# Rev_A.net
KiCad netlist of a schematic drawn in EAGLE
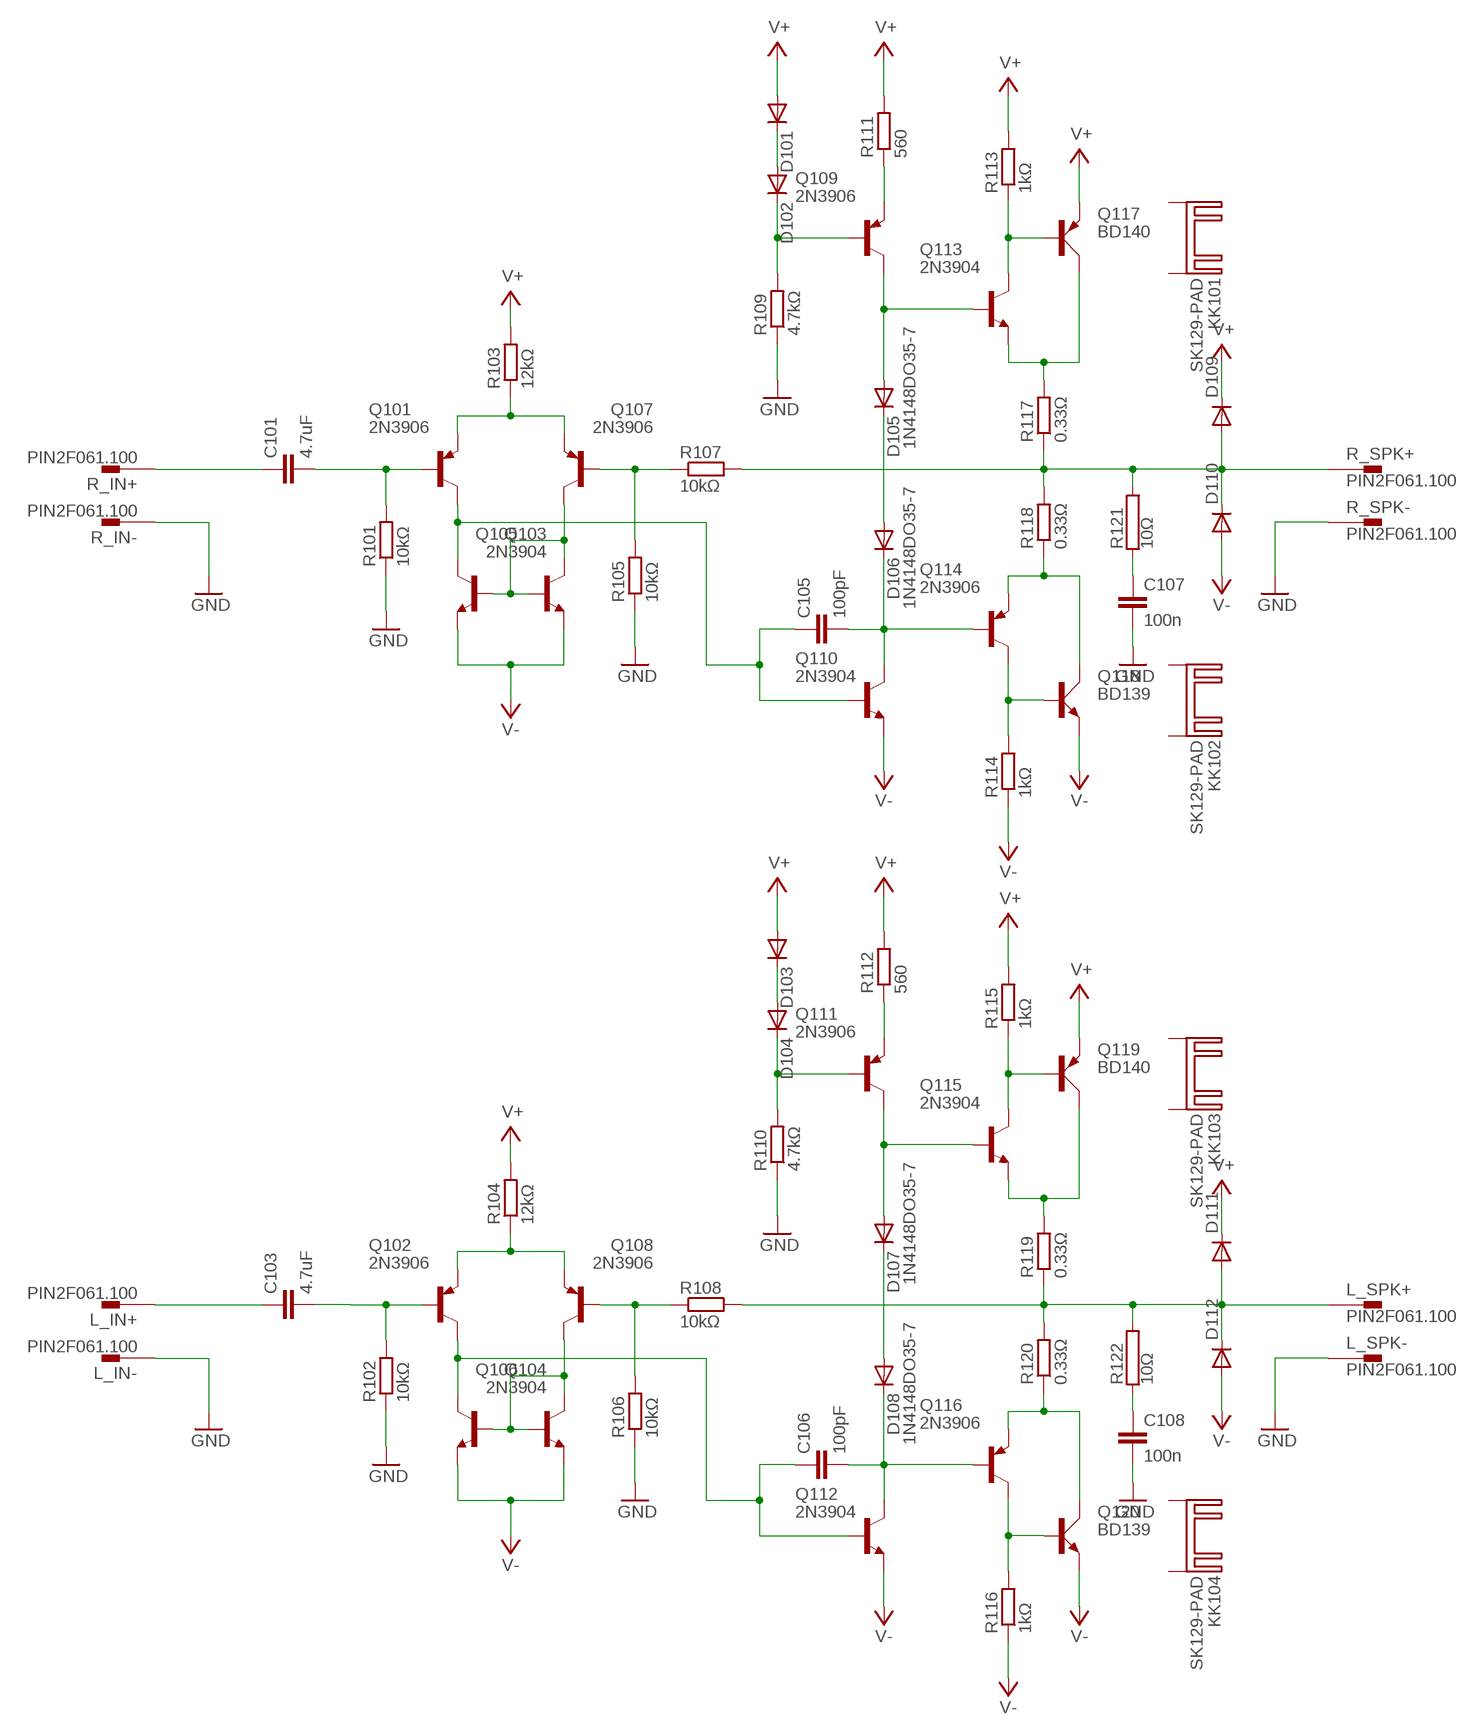
[diagram p0: schematic, sheet 1]
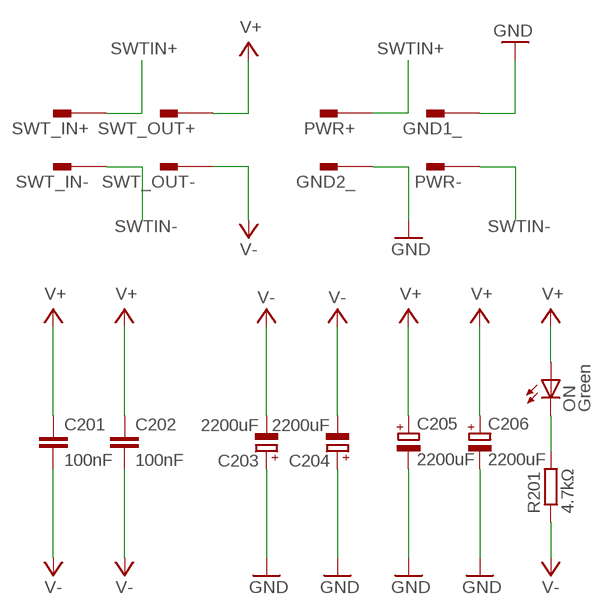
[diagram p1: schematic, sheet 2]

(export (version "E")
  (design (tool "Eeschema 10.0.6"))
  (components
    (comp (ref "C101")
      (value "4.7uF")
      (footprint "eagle-import:C225-113X268")
      (libsource (lib "eagle-import") (part "C-EU225-113X268"))
    )
    (comp (ref "C103")
      (value "4.7uF")
      (footprint "eagle-import:C225-113X268")
      (libsource (lib "eagle-import") (part "C-EU225-113X268"))
    )
    (comp (ref "C105")
      (value "100pF")
      (footprint "eagle-import:C050-050X075")
      (libsource (lib "eagle-import") (part "C-EU050-050X075"))
    )
    (comp (ref "C106")
      (value "100pF")
      (footprint "eagle-import:C050-050X075")
      (libsource (lib "eagle-import") (part "C-EU050-050X075"))
    )
    (comp (ref "C107")
      (value "100n")
      (footprint "eagle-import:C075-042X103")
      (libsource (lib "eagle-import") (part "C-EU075-042X103"))
    )
    (comp (ref "C108")
      (value "100n")
      (footprint "eagle-import:C075-042X103")
      (libsource (lib "eagle-import") (part "C-EU075-042X103"))
    )
    (comp (ref "D101")
      (value "1N4148DO35-7")
      (footprint "eagle-import:DO35-7")
      (libsource (lib "eagle-import") (part "1N4148DO35-7"))
    )
    (comp (ref "D102")
      (value "1N4148DO35-7")
      (footprint "eagle-import:DO35-7")
      (libsource (lib "eagle-import") (part "1N4148DO35-7"))
    )
    (comp (ref "D103")
      (value "1N4148DO35-7")
      (footprint "eagle-import:DO35-7")
      (libsource (lib "eagle-import") (part "1N4148DO35-7"))
    )
    (comp (ref "D104")
      (value "1N4148DO35-7")
      (footprint "eagle-import:DO35-7")
      (libsource (lib "eagle-import") (part "1N4148DO35-7"))
    )
    (comp (ref "D105")
      (value "1N4148DO35-7")
      (footprint "eagle-import:DO35-7")
      (libsource (lib "eagle-import") (part "1N4148DO35-7"))
    )
    (comp (ref "D106")
      (value "1N4148DO35-7")
      (footprint "eagle-import:DO35-7")
      (libsource (lib "eagle-import") (part "1N4148DO35-7"))
    )
    (comp (ref "D107")
      (value "1N4148DO35-7")
      (footprint "eagle-import:DO35-7")
      (libsource (lib "eagle-import") (part "1N4148DO35-7"))
    )
    (comp (ref "D108")
      (value "1N4148DO35-7")
      (footprint "eagle-import:DO35-7")
      (libsource (lib "eagle-import") (part "1N4148DO35-7"))
    )
    (comp (ref "D109")
      (value "1N4148DO35-7")
      (footprint "eagle-import:DO35-7")
      (libsource (lib "eagle-import") (part "1N4148DO35-7"))
    )
    (comp (ref "D110")
      (value "1N4148DO35-7")
      (footprint "eagle-import:DO35-7")
      (libsource (lib "eagle-import") (part "1N4148DO35-7"))
    )
    (comp (ref "D111")
      (value "1N4148DO35-7")
      (footprint "eagle-import:DO35-7")
      (libsource (lib "eagle-import") (part "1N4148DO35-7"))
    )
    (comp (ref "D112")
      (value "1N4148DO35-7")
      (footprint "eagle-import:DO35-7")
      (libsource (lib "eagle-import") (part "1N4148DO35-7"))
    )
    (comp (ref "KK101")
      (value "SK129-PAD")
      (footprint "eagle-import:SK129")
      (libsource (lib "eagle-import") (part "SK129-PAD"))
    )
    (comp (ref "KK102")
      (value "SK129-PAD")
      (footprint "eagle-import:SK129")
      (libsource (lib "eagle-import") (part "SK129-PAD"))
    )
    (comp (ref "KK103")
      (value "SK129-PAD")
      (footprint "eagle-import:SK129")
      (libsource (lib "eagle-import") (part "SK129-PAD"))
    )
    (comp (ref "KK104")
      (value "SK129-PAD")
      (footprint "eagle-import:SK129")
      (libsource (lib "eagle-import") (part "SK129-PAD"))
    )
    (comp (ref "L_IN+")
      (value "PIN2F061.100")
      (footprint "eagle-import:F061.100")
      (libsource (lib "eagle-import") (part "PIN2F061.100"))
    )
    (comp (ref "L_IN-")
      (value "PIN2F061.100")
      (footprint "eagle-import:F061.100")
      (libsource (lib "eagle-import") (part "PIN2F061.100"))
    )
    (comp (ref "L_SPK+")
      (value "PIN2F061.100")
      (footprint "eagle-import:F061.100")
      (libsource (lib "eagle-import") (part "PIN2F061.100"))
    )
    (comp (ref "L_SPK-")
      (value "PIN2F061.100")
      (footprint "eagle-import:F061.100")
      (libsource (lib "eagle-import") (part "PIN2F061.100"))
    )
    (comp (ref "Q101")
      (value "2N3906")
      (footprint "eagle-import:TO92")
      (libsource (lib "eagle-import") (part "2N3906"))
    )
    (comp (ref "Q102")
      (value "2N3906")
      (footprint "eagle-import:TO92")
      (libsource (lib "eagle-import") (part "2N3906"))
    )
    (comp (ref "Q103")
      (value "2N3904")
      (footprint "eagle-import:TO92")
      (libsource (lib "eagle-import") (part "2N3904"))
    )
    (comp (ref "Q104")
      (value "2N3904")
      (footprint "eagle-import:TO92")
      (libsource (lib "eagle-import") (part "2N3904"))
    )
    (comp (ref "Q105")
      (value "2N3904")
      (footprint "eagle-import:TO92")
      (libsource (lib "eagle-import") (part "2N3904"))
    )
    (comp (ref "Q106")
      (value "2N3904")
      (footprint "eagle-import:TO92")
      (libsource (lib "eagle-import") (part "2N3904"))
    )
    (comp (ref "Q107")
      (value "2N3906")
      (footprint "eagle-import:TO92")
      (libsource (lib "eagle-import") (part "2N3906"))
    )
    (comp (ref "Q108")
      (value "2N3906")
      (footprint "eagle-import:TO92")
      (libsource (lib "eagle-import") (part "2N3906"))
    )
    (comp (ref "Q109")
      (value "2N3906")
      (footprint "eagle-import:TO92")
      (libsource (lib "eagle-import") (part "2N3906"))
    )
    (comp (ref "Q110")
      (value "2N3904")
      (footprint "eagle-import:TO92")
      (libsource (lib "eagle-import") (part "2N3904"))
    )
    (comp (ref "Q111")
      (value "2N3906")
      (footprint "eagle-import:TO92")
      (libsource (lib "eagle-import") (part "2N3906"))
    )
    (comp (ref "Q112")
      (value "2N3904")
      (footprint "eagle-import:TO92")
      (libsource (lib "eagle-import") (part "2N3904"))
    )
    (comp (ref "Q113")
      (value "2N3904")
      (footprint "eagle-import:TO92")
      (libsource (lib "eagle-import") (part "2N3904"))
    )
    (comp (ref "Q114")
      (value "2N3906")
      (footprint "eagle-import:TO92")
      (libsource (lib "eagle-import") (part "2N3906"))
    )
    (comp (ref "Q115")
      (value "2N3904")
      (footprint "eagle-import:TO92")
      (libsource (lib "eagle-import") (part "2N3904"))
    )
    (comp (ref "Q116")
      (value "2N3906")
      (footprint "eagle-import:TO92")
      (libsource (lib "eagle-import") (part "2N3906"))
    )
    (comp (ref "Q117")
      (value "BD140")
      (footprint "eagle-import:TO126AV")
      (libsource (lib "eagle-import") (part "BD140"))
    )
    (comp (ref "Q118")
      (value "BD139")
      (footprint "eagle-import:TO126AV")
      (libsource (lib "eagle-import") (part "BD139"))
    )
    (comp (ref "Q119")
      (value "BD140")
      (footprint "eagle-import:TO126AV")
      (libsource (lib "eagle-import") (part "BD140"))
    )
    (comp (ref "Q120")
      (value "BD139")
      (footprint "eagle-import:TO126AV")
      (libsource (lib "eagle-import") (part "BD139"))
    )
    (comp (ref "R101")
      (value "10kΩ")
      (footprint "eagle-import:0207_10")
      (libsource (lib "eagle-import") (part "R-EU_0207/10"))
    )
    (comp (ref "R102")
      (value "10kΩ")
      (footprint "eagle-import:0207_10")
      (libsource (lib "eagle-import") (part "R-EU_0207/10"))
    )
    (comp (ref "R103")
      (value "12kΩ")
      (footprint "eagle-import:0207_10")
      (libsource (lib "eagle-import") (part "R-EU_0207/10"))
    )
    (comp (ref "R104")
      (value "12kΩ")
      (footprint "eagle-import:0207_10")
      (libsource (lib "eagle-import") (part "R-EU_0207/10"))
    )
    (comp (ref "R105")
      (value "10kΩ")
      (footprint "eagle-import:0207_10")
      (libsource (lib "eagle-import") (part "R-EU_0207/10"))
    )
    (comp (ref "R106")
      (value "10kΩ")
      (footprint "eagle-import:0207_10")
      (libsource (lib "eagle-import") (part "R-EU_0207/10"))
    )
    (comp (ref "R107")
      (value "10kΩ")
      (footprint "eagle-import:0207_10")
      (libsource (lib "eagle-import") (part "R-EU_0207/10"))
    )
    (comp (ref "R108")
      (value "10kΩ")
      (footprint "eagle-import:0207_10")
      (libsource (lib "eagle-import") (part "R-EU_0207/10"))
    )
    (comp (ref "R109")
      (value "4.7kΩ")
      (footprint "eagle-import:0207_10")
      (libsource (lib "eagle-import") (part "R-EU_0207/10"))
    )
    (comp (ref "R110")
      (value "4.7kΩ")
      (footprint "eagle-import:0207_10")
      (libsource (lib "eagle-import") (part "R-EU_0207/10"))
    )
    (comp (ref "R111")
      (value "560")
      (footprint "eagle-import:0207_10")
      (libsource (lib "eagle-import") (part "R-EU_0207/10"))
    )
    (comp (ref "R112")
      (value "560")
      (footprint "eagle-import:0207_10")
      (libsource (lib "eagle-import") (part "R-EU_0207/10"))
    )
    (comp (ref "R113")
      (value "1kΩ")
      (footprint "eagle-import:0207_10")
      (libsource (lib "eagle-import") (part "R-EU_0207/10"))
    )
    (comp (ref "R114")
      (value "1kΩ")
      (footprint "eagle-import:0207_10")
      (libsource (lib "eagle-import") (part "R-EU_0207/10"))
    )
    (comp (ref "R115")
      (value "1kΩ")
      (footprint "eagle-import:0207_10")
      (libsource (lib "eagle-import") (part "R-EU_0207/10"))
    )
    (comp (ref "R116")
      (value "1kΩ")
      (footprint "eagle-import:0207_10")
      (libsource (lib "eagle-import") (part "R-EU_0207/10"))
    )
    (comp (ref "R117")
      (value "0.33Ω")
      (footprint "eagle-import:0309_12")
      (libsource (lib "eagle-import") (part "R-EU_0309/12"))
    )
    (comp (ref "R118")
      (value "0.33Ω")
      (footprint "eagle-import:0309_12")
      (libsource (lib "eagle-import") (part "R-EU_0309/12"))
    )
    (comp (ref "R119")
      (value "0.33Ω")
      (footprint "eagle-import:0309_12")
      (libsource (lib "eagle-import") (part "R-EU_0309/12"))
    )
    (comp (ref "R120")
      (value "0.33Ω")
      (footprint "eagle-import:0309_12")
      (libsource (lib "eagle-import") (part "R-EU_0309/12"))
    )
    (comp (ref "R121")
      (value "10Ω")
      (footprint "eagle-import:MNS-5")
      (libsource (lib "eagle-import") (part "RMNS-5"))
    )
    (comp (ref "R122")
      (value "10Ω")
      (footprint "eagle-import:MNS-5")
      (libsource (lib "eagle-import") (part "RMNS-5"))
    )
    (comp (ref "R_IN+")
      (value "PIN2F061.100")
      (footprint "eagle-import:F061.100")
      (libsource (lib "eagle-import") (part "PIN2F061.100"))
    )
    (comp (ref "R_IN-")
      (value "PIN2F061.100")
      (footprint "eagle-import:F061.100")
      (libsource (lib "eagle-import") (part "PIN2F061.100"))
    )
    (comp (ref "R_SPK+")
      (value "PIN2F061.100")
      (footprint "eagle-import:F061.100")
      (libsource (lib "eagle-import") (part "PIN2F061.100"))
    )
    (comp (ref "R_SPK-")
      (value "PIN2F061.100")
      (footprint "eagle-import:F061.100")
      (libsource (lib "eagle-import") (part "PIN2F061.100"))
    )
    (comp (ref "C201")
      (value "100nF")
      (footprint "eagle-import:C025-025X050")
      (libsource (lib "eagle-import") (part "C-EU025-025X050"))
    )
    (comp (ref "C202")
      (value "100nF")
      (footprint "eagle-import:C025-025X050")
      (libsource (lib "eagle-import") (part "C-EU025-025X050"))
    )
    (comp (ref "C203")
      (value "2200uF")
      (footprint "eagle-import:E5-10,5")
      (libsource (lib "eagle-import") (part "CPOL-EUE5-10.5"))
    )
    (comp (ref "C204")
      (value "2200uF")
      (footprint "eagle-import:E5-10,5")
      (libsource (lib "eagle-import") (part "CPOL-EUE5-10.5"))
    )
    (comp (ref "C205")
      (value "2200uF")
      (footprint "eagle-import:E5-10,5")
      (libsource (lib "eagle-import") (part "CPOL-EUE5-10.5"))
    )
    (comp (ref "C206")
      (value "2200uF")
      (footprint "eagle-import:E5-10,5")
      (libsource (lib "eagle-import") (part "CPOL-EUE5-10.5"))
    )
    (comp (ref "GND1_")
      (value "PIN2F061.100")
      (footprint "eagle-import:F061.100")
      (libsource (lib "eagle-import") (part "PIN2F061.100"))
    )
    (comp (ref "GND2_")
      (value "PIN2F061.100")
      (footprint "eagle-import:F061.100")
      (libsource (lib "eagle-import") (part "PIN2F061.100"))
    )
    (comp (ref "ON")
      (value "Green")
      (footprint "eagle-import:LED5MM")
      (libsource (lib "eagle-import") (part "LED5MM"))
    )
    (comp (ref "PWR+")
      (value "PIN2F061.100")
      (footprint "eagle-import:F061.100")
      (libsource (lib "eagle-import") (part "PIN2F061.100"))
    )
    (comp (ref "PWR-")
      (value "PIN2F061.100")
      (footprint "eagle-import:F061.100")
      (libsource (lib "eagle-import") (part "PIN2F061.100"))
    )
    (comp (ref "R201")
      (value "4.7kΩ")
      (footprint "eagle-import:0207_10")
      (libsource (lib "eagle-import") (part "R-EU_0207/10"))
    )
    (comp (ref "SWT_IN+")
      (value "PIN2F061.100")
      (footprint "eagle-import:F061.100")
      (libsource (lib "eagle-import") (part "PIN2F061.100"))
    )
    (comp (ref "SWT_IN-")
      (value "PIN2F061.100")
      (footprint "eagle-import:F061.100")
      (libsource (lib "eagle-import") (part "PIN2F061.100"))
    )
    (comp (ref "SWT_OUT+")
      (value "PIN2F061.100")
      (footprint "eagle-import:F061.100")
      (libsource (lib "eagle-import") (part "PIN2F061.100"))
    )
    (comp (ref "SWT_OUT-")
      (value "PIN2F061.100")
      (footprint "eagle-import:F061.100")
      (libsource (lib "eagle-import") (part "PIN2F061.100"))
    )
  )
  (nets
    (net (code "1") (name "GND") (class "Default")
      (node (ref "C107") (pin "2") (pinfunction "2_2") (pintype "passive"))
      (node (ref "C108") (pin "2") (pinfunction "2_2") (pintype "passive"))
      (node (ref "C203") (pin "+") (pinfunction "+_+") (pintype "passive"))
      (node (ref "C204") (pin "+") (pinfunction "+_+") (pintype "passive"))
      (node (ref "C205") (pin "-") (pinfunction "-_-") (pintype "passive"))
      (node (ref "C206") (pin "-") (pinfunction "-_-") (pintype "passive"))
      (node (ref "GND1_") (pin "A1") (pinfunction "1_A1") (pintype "passive"))
      (node (ref "GND1_") (pin "A2") (pinfunction "1_A2") (pintype "passive"))
      (node (ref "GND2_") (pin "A1") (pinfunction "1_A1") (pintype "passive"))
      (node (ref "GND2_") (pin "A2") (pinfunction "1_A2") (pintype "passive"))
      (node (ref "L_IN-") (pin "A1") (pinfunction "1_A1") (pintype "passive"))
      (node (ref "L_IN-") (pin "A2") (pinfunction "1_A2") (pintype "passive"))
      (node (ref "L_SPK-") (pin "A1") (pinfunction "1_A1") (pintype "passive"))
      (node (ref "L_SPK-") (pin "A2") (pinfunction "1_A2") (pintype "passive"))
      (node (ref "R101") (pin "1") (pinfunction "1_1") (pintype "passive"))
      (node (ref "R102") (pin "1") (pinfunction "1_1") (pintype "passive"))
      (node (ref "R105") (pin "1") (pinfunction "1_1") (pintype "passive"))
      (node (ref "R106") (pin "1") (pinfunction "1_1") (pintype "passive"))
      (node (ref "R109") (pin "1") (pinfunction "1_1") (pintype "passive"))
      (node (ref "R110") (pin "1") (pinfunction "1_1") (pintype "passive"))
      (node (ref "R_IN-") (pin "A1") (pinfunction "1_A1") (pintype "passive"))
      (node (ref "R_IN-") (pin "A2") (pinfunction "1_A2") (pintype "passive"))
      (node (ref "R_SPK-") (pin "A1") (pinfunction "1_A1") (pintype "passive"))
      (node (ref "R_SPK-") (pin "A2") (pinfunction "1_A2") (pintype "passive"))
    )
    (net (code "2") (name "Net-(C101-Pad1)") (class "Default")
      (node (ref "C101") (pin "1") (pinfunction "1_1") (pintype "passive"))
      (node (ref "R_IN+") (pin "A1") (pinfunction "1_A1") (pintype "passive"))
      (node (ref "R_IN+") (pin "A2") (pinfunction "1_A2") (pintype "passive"))
    )
    (net (code "3") (name "Net-(C103-Pad1)") (class "Default")
      (node (ref "C103") (pin "1") (pinfunction "1_1") (pintype "passive"))
      (node (ref "L_IN+") (pin "A1") (pinfunction "1_A1") (pintype "passive"))
      (node (ref "L_IN+") (pin "A2") (pinfunction "1_A2") (pintype "passive"))
    )
    (net (code "4") (name "Net-(C107-Pad1)") (class "Default")
      (node (ref "C107") (pin "1") (pinfunction "1_1") (pintype "passive"))
      (node (ref "R121") (pin "1") (pinfunction "1_1") (pintype "passive"))
    )
    (net (code "5") (name "Net-(C108-Pad1)") (class "Default")
      (node (ref "C108") (pin "1") (pinfunction "1_1") (pintype "passive"))
      (node (ref "R122") (pin "1") (pinfunction "1_1") (pintype "passive"))
    )
    (net (code "6") (name "Net-(D101-PadC)") (class "Default")
      (node (ref "D101") (pin "C") (pinfunction "C_C") (pintype "passive"))
      (node (ref "D102") (pin "A") (pinfunction "A_A") (pintype "passive"))
    )
    (net (code "7") (name "Net-(D103-PadC)") (class "Default")
      (node (ref "D103") (pin "C") (pinfunction "C_C") (pintype "passive"))
      (node (ref "D104") (pin "A") (pinfunction "A_A") (pintype "passive"))
    )
    (net (code "8") (name "Net-(D105-PadC)") (class "Default")
      (node (ref "D105") (pin "C") (pinfunction "C_C") (pintype "passive"))
      (node (ref "D106") (pin "A") (pinfunction "A_A") (pintype "passive"))
    )
    (net (code "9") (name "Net-(D107-PadC)") (class "Default")
      (node (ref "D107") (pin "C") (pinfunction "C_C") (pintype "passive"))
      (node (ref "D108") (pin "A") (pinfunction "A_A") (pintype "passive"))
    )
    (net (code "10") (name "Net-(D109-PadA)") (class "Default")
      (node (ref "D109") (pin "A") (pinfunction "A_A") (pintype "passive"))
      (node (ref "D110") (pin "C") (pinfunction "C_C") (pintype "passive"))
      (node (ref "R107") (pin "2") (pinfunction "2_2") (pintype "passive"))
      (node (ref "R117") (pin "1") (pinfunction "1_1") (pintype "passive"))
      (node (ref "R118") (pin "2") (pinfunction "2_2") (pintype "passive"))
      (node (ref "R121") (pin "2") (pinfunction "2_2") (pintype "passive"))
      (node (ref "R_SPK+") (pin "A1") (pinfunction "1_A1") (pintype "passive"))
      (node (ref "R_SPK+") (pin "A2") (pinfunction "1_A2") (pintype "passive"))
    )
    (net (code "11") (name "Net-(D111-PadA)") (class "Default")
      (node (ref "D111") (pin "A") (pinfunction "A_A") (pintype "passive"))
      (node (ref "D112") (pin "C") (pinfunction "C_C") (pintype "passive"))
      (node (ref "L_SPK+") (pin "A1") (pinfunction "1_A1") (pintype "passive"))
      (node (ref "L_SPK+") (pin "A2") (pinfunction "1_A2") (pintype "passive"))
      (node (ref "R108") (pin "2") (pinfunction "2_2") (pintype "passive"))
      (node (ref "R119") (pin "1") (pinfunction "1_1") (pintype "passive"))
      (node (ref "R120") (pin "2") (pinfunction "2_2") (pintype "passive"))
      (node (ref "R122") (pin "2") (pinfunction "2_2") (pintype "passive"))
    )
    (net (code "12") (name "Net-(ON-C)") (class "Default")
      (node (ref "ON") (pin "K") (pinfunction "C_K") (pintype "passive"))
      (node (ref "R201") (pin "2") (pinfunction "2_2") (pintype "passive"))
    )
    (net (code "13") (name "Net-(Q101-B)") (class "Default")
      (node (ref "C101") (pin "2") (pinfunction "2_2") (pintype "passive"))
      (node (ref "Q101") (pin "2") (pinfunction "B_2") (pintype "passive"))
      (node (ref "R101") (pin "2") (pinfunction "2_2") (pintype "passive"))
    )
    (net (code "14") (name "Net-(Q101-C)") (class "Default")
      (node (ref "C105") (pin "1") (pinfunction "1_1") (pintype "passive"))
      (node (ref "Q101") (pin "1") (pinfunction "C_1") (pintype "passive"))
      (node (ref "Q103") (pin "1") (pinfunction "C_1") (pintype "passive"))
      (node (ref "Q110") (pin "2") (pinfunction "B_2") (pintype "passive"))
    )
    (net (code "15") (name "Net-(Q101-E)") (class "Default")
      (node (ref "Q101") (pin "3") (pinfunction "E_3") (pintype "passive"))
      (node (ref "Q107") (pin "3") (pinfunction "E_3") (pintype "passive"))
      (node (ref "R103") (pin "1") (pinfunction "1_1") (pintype "passive"))
    )
    (net (code "16") (name "Net-(Q102-B)") (class "Default")
      (node (ref "C103") (pin "2") (pinfunction "2_2") (pintype "passive"))
      (node (ref "Q102") (pin "2") (pinfunction "B_2") (pintype "passive"))
      (node (ref "R102") (pin "2") (pinfunction "2_2") (pintype "passive"))
    )
    (net (code "17") (name "Net-(Q102-C)") (class "Default")
      (node (ref "C106") (pin "1") (pinfunction "1_1") (pintype "passive"))
      (node (ref "Q102") (pin "1") (pinfunction "C_1") (pintype "passive"))
      (node (ref "Q104") (pin "1") (pinfunction "C_1") (pintype "passive"))
      (node (ref "Q112") (pin "2") (pinfunction "B_2") (pintype "passive"))
    )
    (net (code "18") (name "Net-(Q102-E)") (class "Default")
      (node (ref "Q102") (pin "3") (pinfunction "E_3") (pintype "passive"))
      (node (ref "Q108") (pin "3") (pinfunction "E_3") (pintype "passive"))
      (node (ref "R104") (pin "1") (pinfunction "1_1") (pintype "passive"))
    )
    (net (code "19") (name "Net-(Q103-B)") (class "Default")
      (node (ref "Q103") (pin "2") (pinfunction "B_2") (pintype "passive"))
      (node (ref "Q105") (pin "1") (pinfunction "C_1") (pintype "passive"))
      (node (ref "Q105") (pin "2") (pinfunction "B_2") (pintype "passive"))
      (node (ref "Q107") (pin "1") (pinfunction "C_1") (pintype "passive"))
    )
    (net (code "20") (name "Net-(Q104-B)") (class "Default")
      (node (ref "Q104") (pin "2") (pinfunction "B_2") (pintype "passive"))
      (node (ref "Q106") (pin "1") (pinfunction "C_1") (pintype "passive"))
      (node (ref "Q106") (pin "2") (pinfunction "B_2") (pintype "passive"))
      (node (ref "Q108") (pin "1") (pinfunction "C_1") (pintype "passive"))
    )
    (net (code "21") (name "Net-(Q107-B)") (class "Default")
      (node (ref "Q107") (pin "2") (pinfunction "B_2") (pintype "passive"))
      (node (ref "R105") (pin "2") (pinfunction "2_2") (pintype "passive"))
      (node (ref "R107") (pin "1") (pinfunction "1_1") (pintype "passive"))
    )
    (net (code "22") (name "Net-(Q108-B)") (class "Default")
      (node (ref "Q108") (pin "2") (pinfunction "B_2") (pintype "passive"))
      (node (ref "R106") (pin "2") (pinfunction "2_2") (pintype "passive"))
      (node (ref "R108") (pin "1") (pinfunction "1_1") (pintype "passive"))
    )
    (net (code "23") (name "Net-(Q109-B)") (class "Default")
      (node (ref "D102") (pin "C") (pinfunction "C_C") (pintype "passive"))
      (node (ref "Q109") (pin "2") (pinfunction "B_2") (pintype "passive"))
      (node (ref "R109") (pin "2") (pinfunction "2_2") (pintype "passive"))
    )
    (net (code "24") (name "Net-(Q109-C)") (class "Default")
      (node (ref "D105") (pin "A") (pinfunction "A_A") (pintype "passive"))
      (node (ref "Q109") (pin "1") (pinfunction "C_1") (pintype "passive"))
      (node (ref "Q113") (pin "2") (pinfunction "B_2") (pintype "passive"))
    )
    (net (code "25") (name "Net-(Q109-E)") (class "Default")
      (node (ref "Q109") (pin "3") (pinfunction "E_3") (pintype "passive"))
      (node (ref "R111") (pin "1") (pinfunction "1_1") (pintype "passive"))
    )
    (net (code "26") (name "Net-(Q110-C)") (class "Default")
      (node (ref "C105") (pin "2") (pinfunction "2_2") (pintype "passive"))
      (node (ref "D106") (pin "C") (pinfunction "C_C") (pintype "passive"))
      (node (ref "Q110") (pin "1") (pinfunction "C_1") (pintype "passive"))
      (node (ref "Q114") (pin "2") (pinfunction "B_2") (pintype "passive"))
    )
    (net (code "27") (name "Net-(Q111-B)") (class "Default")
      (node (ref "D104") (pin "C") (pinfunction "C_C") (pintype "passive"))
      (node (ref "Q111") (pin "2") (pinfunction "B_2") (pintype "passive"))
      (node (ref "R110") (pin "2") (pinfunction "2_2") (pintype "passive"))
    )
    (net (code "28") (name "Net-(Q111-C)") (class "Default")
      (node (ref "D107") (pin "A") (pinfunction "A_A") (pintype "passive"))
      (node (ref "Q111") (pin "1") (pinfunction "C_1") (pintype "passive"))
      (node (ref "Q115") (pin "2") (pinfunction "B_2") (pintype "passive"))
    )
    (net (code "29") (name "Net-(Q111-E)") (class "Default")
      (node (ref "Q111") (pin "3") (pinfunction "E_3") (pintype "passive"))
      (node (ref "R112") (pin "1") (pinfunction "1_1") (pintype "passive"))
    )
    (net (code "30") (name "Net-(Q112-C)") (class "Default")
      (node (ref "C106") (pin "2") (pinfunction "2_2") (pintype "passive"))
      (node (ref "D108") (pin "C") (pinfunction "C_C") (pintype "passive"))
      (node (ref "Q112") (pin "1") (pinfunction "C_1") (pintype "passive"))
      (node (ref "Q116") (pin "2") (pinfunction "B_2") (pintype "passive"))
    )
    (net (code "31") (name "Net-(Q113-C)") (class "Default")
      (node (ref "Q113") (pin "1") (pinfunction "C_1") (pintype "passive"))
      (node (ref "Q117") (pin "B") (pinfunction "B_B") (pintype "passive"))
      (node (ref "R113") (pin "1") (pinfunction "1_1") (pintype "passive"))
    )
    (net (code "32") (name "Net-(Q113-E)") (class "Default")
      (node (ref "Q113") (pin "3") (pinfunction "E_3") (pintype "passive"))
      (node (ref "Q117") (pin "C") (pinfunction "C_C") (pintype "passive"))
      (node (ref "R117") (pin "2") (pinfunction "2_2") (pintype "passive"))
    )
    (net (code "33") (name "Net-(Q114-C)") (class "Default")
      (node (ref "Q114") (pin "1") (pinfunction "C_1") (pintype "passive"))
      (node (ref "Q118") (pin "B") (pinfunction "B_B") (pintype "passive"))
      (node (ref "R114") (pin "2") (pinfunction "2_2") (pintype "passive"))
    )
    (net (code "34") (name "Net-(Q114-E)") (class "Default")
      (node (ref "Q114") (pin "3") (pinfunction "E_3") (pintype "passive"))
      (node (ref "Q118") (pin "C") (pinfunction "C_C") (pintype "passive"))
      (node (ref "R118") (pin "1") (pinfunction "1_1") (pintype "passive"))
    )
    (net (code "35") (name "Net-(Q115-C)") (class "Default")
      (node (ref "Q115") (pin "1") (pinfunction "C_1") (pintype "passive"))
      (node (ref "Q119") (pin "B") (pinfunction "B_B") (pintype "passive"))
      (node (ref "R115") (pin "1") (pinfunction "1_1") (pintype "passive"))
    )
    (net (code "36") (name "Net-(Q115-E)") (class "Default")
      (node (ref "Q115") (pin "3") (pinfunction "E_3") (pintype "passive"))
      (node (ref "Q119") (pin "C") (pinfunction "C_C") (pintype "passive"))
      (node (ref "R119") (pin "2") (pinfunction "2_2") (pintype "passive"))
    )
    (net (code "37") (name "Net-(Q116-C)") (class "Default")
      (node (ref "Q116") (pin "1") (pinfunction "C_1") (pintype "passive"))
      (node (ref "Q120") (pin "B") (pinfunction "B_B") (pintype "passive"))
      (node (ref "R116") (pin "2") (pinfunction "2_2") (pintype "passive"))
    )
    (net (code "38") (name "Net-(Q116-E)") (class "Default")
      (node (ref "Q116") (pin "3") (pinfunction "E_3") (pintype "passive"))
      (node (ref "Q120") (pin "C") (pinfunction "C_C") (pintype "passive"))
      (node (ref "R120") (pin "1") (pinfunction "1_1") (pintype "passive"))
    )
    (net (code "39") (name "SWTIN+") (class "Default")
      (node (ref "PWR+") (pin "A1") (pinfunction "1_A1") (pintype "passive"))
      (node (ref "PWR+") (pin "A2") (pinfunction "1_A2") (pintype "passive"))
      (node (ref "SWT_IN+") (pin "A1") (pinfunction "1_A1") (pintype "passive"))
      (node (ref "SWT_IN+") (pin "A2") (pinfunction "1_A2") (pintype "passive"))
    )
    (net (code "40") (name "SWTIN-") (class "Default")
      (node (ref "PWR-") (pin "A1") (pinfunction "1_A1") (pintype "passive"))
      (node (ref "PWR-") (pin "A2") (pinfunction "1_A2") (pintype "passive"))
      (node (ref "SWT_IN-") (pin "A1") (pinfunction "1_A1") (pintype "passive"))
      (node (ref "SWT_IN-") (pin "A2") (pinfunction "1_A2") (pintype "passive"))
    )
    (net (code "41") (name "V+") (class "Default")
      (node (ref "C201") (pin "1") (pinfunction "1_1") (pintype "passive"))
      (node (ref "C202") (pin "1") (pinfunction "1_1") (pintype "passive"))
      (node (ref "C205") (pin "+") (pinfunction "+_+") (pintype "passive"))
      (node (ref "C206") (pin "+") (pinfunction "+_+") (pintype "passive"))
      (node (ref "D101") (pin "A") (pinfunction "A_A") (pintype "passive"))
      (node (ref "D103") (pin "A") (pinfunction "A_A") (pintype "passive"))
      (node (ref "D109") (pin "C") (pinfunction "C_C") (pintype "passive"))
      (node (ref "D111") (pin "C") (pinfunction "C_C") (pintype "passive"))
      (node (ref "ON") (pin "A") (pinfunction "A_A") (pintype "passive"))
      (node (ref "Q117") (pin "E") (pinfunction "E_E") (pintype "passive"))
      (node (ref "Q119") (pin "E") (pinfunction "E_E") (pintype "passive"))
      (node (ref "R103") (pin "2") (pinfunction "2_2") (pintype "passive"))
      (node (ref "R104") (pin "2") (pinfunction "2_2") (pintype "passive"))
      (node (ref "R111") (pin "2") (pinfunction "2_2") (pintype "passive"))
      (node (ref "R112") (pin "2") (pinfunction "2_2") (pintype "passive"))
      (node (ref "R113") (pin "2") (pinfunction "2_2") (pintype "passive"))
      (node (ref "R115") (pin "2") (pinfunction "2_2") (pintype "passive"))
      (node (ref "SWT_OUT+") (pin "A1") (pinfunction "1_A1") (pintype "passive"))
      (node (ref "SWT_OUT+") (pin "A2") (pinfunction "1_A2") (pintype "passive"))
    )
    (net (code "42") (name "V-") (class "Default")
      (node (ref "C201") (pin "2") (pinfunction "2_2") (pintype "passive"))
      (node (ref "C202") (pin "2") (pinfunction "2_2") (pintype "passive"))
      (node (ref "C203") (pin "-") (pinfunction "-_-") (pintype "passive"))
      (node (ref "C204") (pin "-") (pinfunction "-_-") (pintype "passive"))
      (node (ref "D110") (pin "A") (pinfunction "A_A") (pintype "passive"))
      (node (ref "D112") (pin "A") (pinfunction "A_A") (pintype "passive"))
      (node (ref "Q103") (pin "3") (pinfunction "E_3") (pintype "passive"))
      (node (ref "Q104") (pin "3") (pinfunction "E_3") (pintype "passive"))
      (node (ref "Q105") (pin "3") (pinfunction "E_3") (pintype "passive"))
      (node (ref "Q106") (pin "3") (pinfunction "E_3") (pintype "passive"))
      (node (ref "Q110") (pin "3") (pinfunction "E_3") (pintype "passive"))
      (node (ref "Q112") (pin "3") (pinfunction "E_3") (pintype "passive"))
      (node (ref "Q118") (pin "E") (pinfunction "E_E") (pintype "passive"))
      (node (ref "Q120") (pin "E") (pinfunction "E_E") (pintype "passive"))
      (node (ref "R114") (pin "1") (pinfunction "1_1") (pintype "passive"))
      (node (ref "R116") (pin "1") (pinfunction "1_1") (pintype "passive"))
      (node (ref "R201") (pin "1") (pinfunction "1_1") (pintype "passive"))
      (node (ref "SWT_OUT-") (pin "A1") (pinfunction "1_A1") (pintype "passive"))
      (node (ref "SWT_OUT-") (pin "A2") (pinfunction "1_A2") (pintype "passive"))
    )
    (net (code "43") (name "unconnected-(KK101-K-PadA2,5)") (class "Default")
      (node (ref "KK101") (pin "A2,5") (pinfunction "K_A2,5") (pintype "passive"))
    )
    (net (code "44") (name "unconnected-(KK101-K-PadB2,5)") (class "Default")
      (node (ref "KK101") (pin "B2,5") (pinfunction "K_B2,5") (pintype "passive"))
    )
    (net (code "45") (name "unconnected-(KK102-K-PadA2,5)") (class "Default")
      (node (ref "KK102") (pin "A2,5") (pinfunction "K_A2,5") (pintype "passive"))
    )
    (net (code "46") (name "unconnected-(KK102-K-PadB2,5)") (class "Default")
      (node (ref "KK102") (pin "B2,5") (pinfunction "K_B2,5") (pintype "passive"))
    )
    (net (code "47") (name "unconnected-(KK103-K-PadA2,5)") (class "Default")
      (node (ref "KK103") (pin "A2,5") (pinfunction "K_A2,5") (pintype "passive"))
    )
    (net (code "48") (name "unconnected-(KK103-K-PadB2,5)") (class "Default")
      (node (ref "KK103") (pin "B2,5") (pinfunction "K_B2,5") (pintype "passive"))
    )
    (net (code "49") (name "unconnected-(KK104-K-PadA2,5)") (class "Default")
      (node (ref "KK104") (pin "A2,5") (pinfunction "K_A2,5") (pintype "passive"))
    )
    (net (code "50") (name "unconnected-(KK104-K-PadB2,5)") (class "Default")
      (node (ref "KK104") (pin "B2,5") (pinfunction "K_B2,5") (pintype "passive"))
    )
  )
)
